# Finishline_Controller.net
KiCad netlist of a schematic drawn in EAGLE
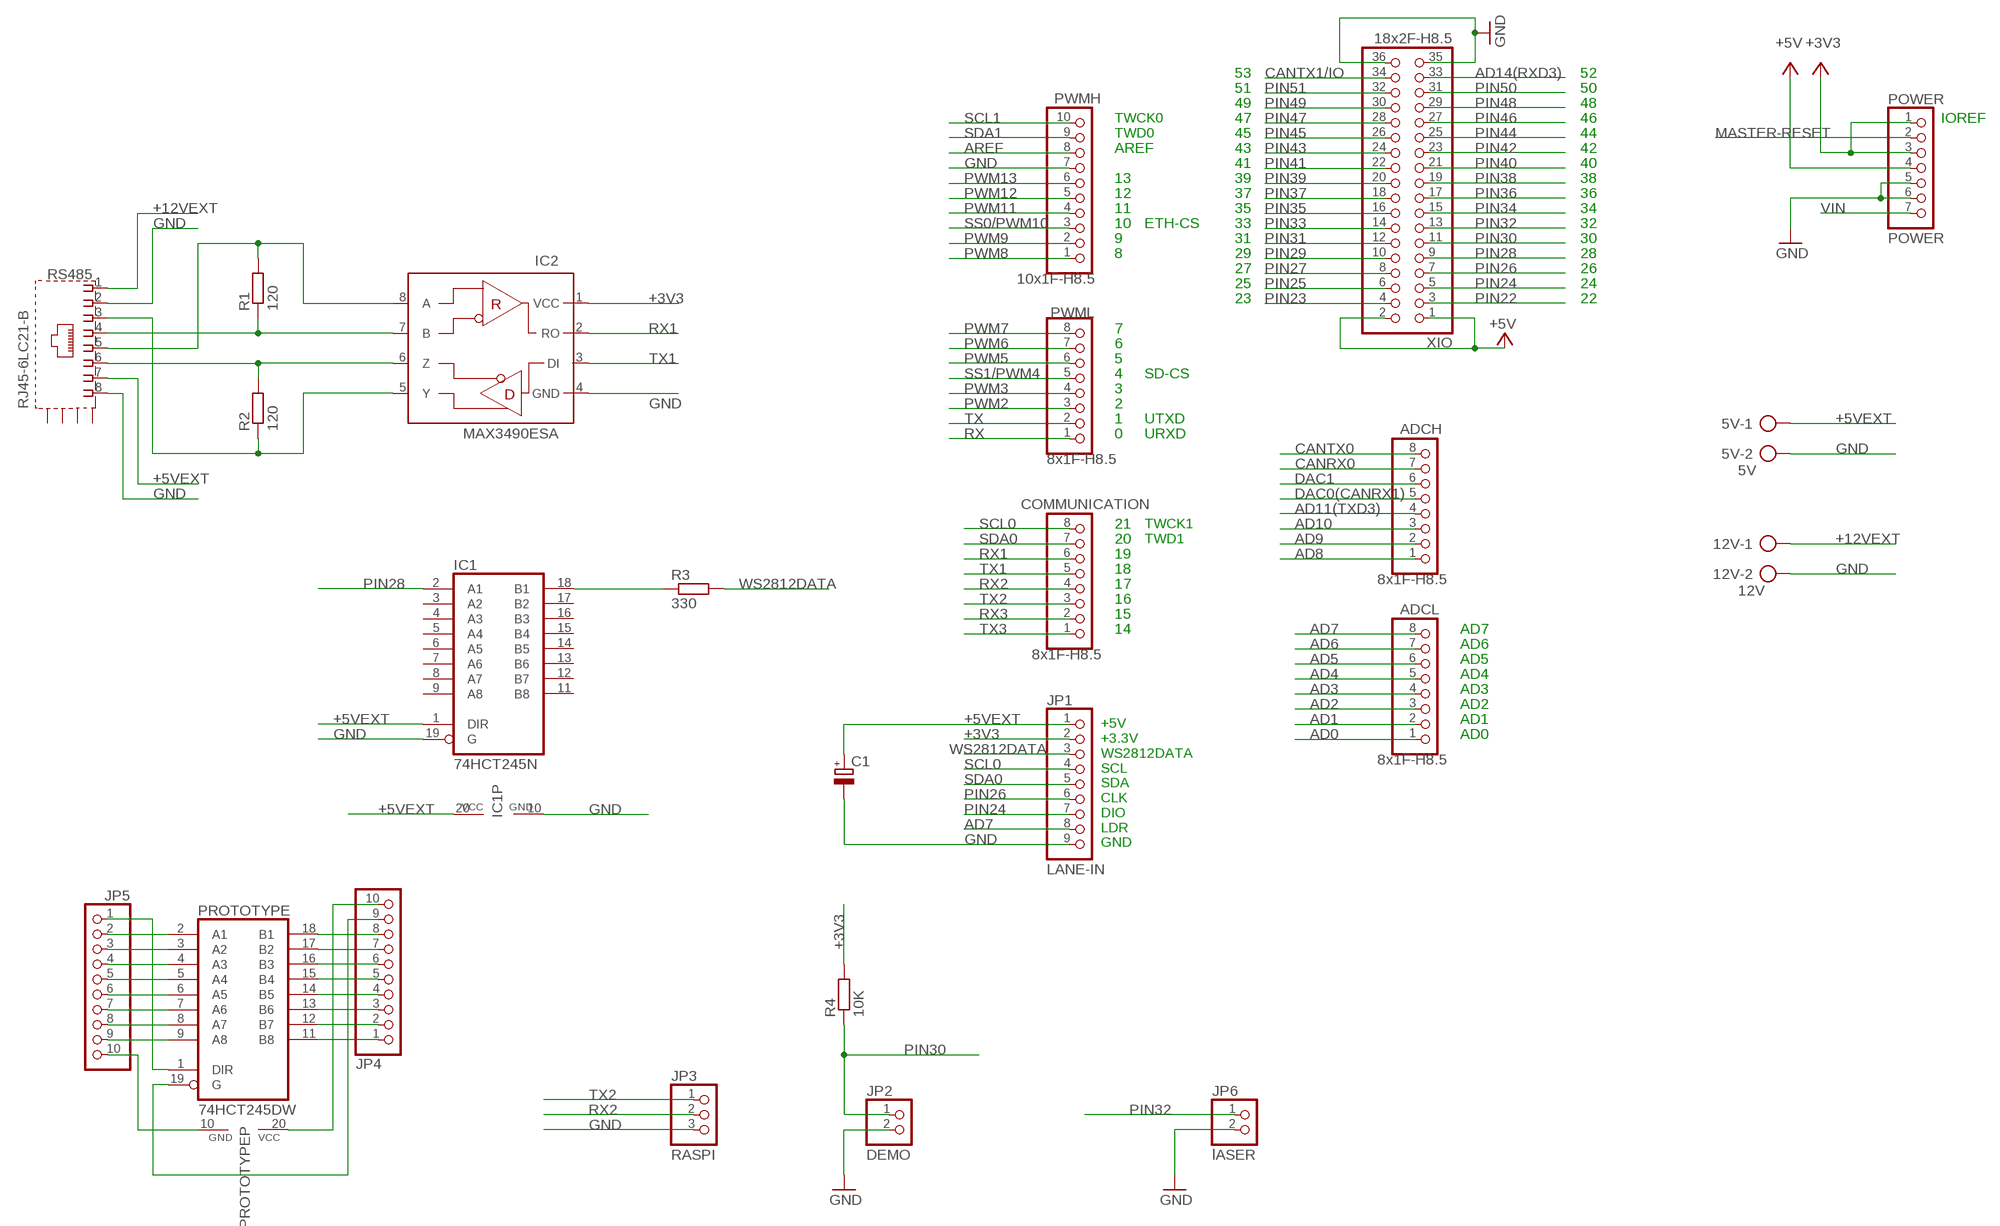
[diagram p0: schematic, sheet 1]

(export (version "E")
  (design (tool "Eeschema 10.0.6"))
  (components
    (comp (ref "5V")
      (value "5V")
      (footprint "eagle-import:AK300_2")
      (libsource (lib "eagle-import") (part "AK300/2"))
    )
    (comp (ref "12V")
      (value "12V")
      (footprint "eagle-import:AK300_2")
      (libsource (lib "eagle-import") (part "AK300/2"))
    )
    (comp (ref "ADCH")
      (value "8x1F-H8.5")
      (footprint "eagle-import:1X08")
      (libsource (lib "eagle-import") (part "PINHD-1X8"))
    )
    (comp (ref "ADCL")
      (value "8x1F-H8.5")
      (footprint "eagle-import:1X08")
      (libsource (lib "eagle-import") (part "PINHD-1X8"))
    )
    (comp (ref "C1")
      (value "CPOL-EUE5-10.5")
      (footprint "eagle-import:E5-10,5")
      (libsource (lib "eagle-import") (part "CPOL-EUE5-10.5"))
    )
    (comp (ref "COMMUNICATION")
      (value "8x1F-H8.5")
      (footprint "eagle-import:1X08")
      (libsource (lib "eagle-import") (part "PINHD-1X8"))
    )
    (comp (ref "IC1")
      (value "74HCT245N")
      (footprint "eagle-import:DIL20")
      (libsource (lib "eagle-import") (part "74245NHCT"))
    )
    (comp (ref "IC2")
      (value "MAX3490ESA")
      (footprint "eagle-import:SO08")
      (libsource (lib "eagle-import") (part "MAX3490ESA"))
    )
    (comp (ref "JP1")
      (value "LANE-IN")
      (footprint "eagle-import:1X09")
      (libsource (lib "eagle-import") (part "PINHD-1X9"))
    )
    (comp (ref "JP2")
      (value "DEMO")
      (footprint "eagle-import:1X02")
      (libsource (lib "eagle-import") (part "PINHD-1X2"))
    )
    (comp (ref "JP3")
      (value "RASPI")
      (footprint "eagle-import:1X03")
      (libsource (lib "eagle-import") (part "PINHD-1X3"))
    )
    (comp (ref "JP4")
      (value "PINHD-1X10")
      (footprint "eagle-import:1X10")
      (libsource (lib "eagle-import") (part "pinhead_PINHD-1X10"))
    )
    (comp (ref "JP5")
      (value "PINHD-1X10")
      (footprint "eagle-import:1X10")
      (libsource (lib "eagle-import") (part "pinhead_PINHD-1X10"))
    )
    (comp (ref "JP6")
      (value "lASER")
      (footprint "eagle-import:1X02")
      (libsource (lib "eagle-import") (part "PINHD-1X2"))
    )
    (comp (ref "POWER")
      (value "POWER")
      (footprint "eagle-import:1X07")
      (libsource (lib "eagle-import") (part "PINHD-1X7"))
    )
    (comp (ref "PROTOTYPE")
      (value "74HCT245DW")
      (footprint "eagle-import:SO20W")
      (libsource (lib "eagle-import") (part "74245DWHCT"))
    )
    (comp (ref "PWMH")
      (value "10x1F-H8.5")
      (footprint "eagle-import:1X10")
      (libsource (lib "eagle-import") (part "PINHD-1X10"))
    )
    (comp (ref "PWML")
      (value "8x1F-H8.5")
      (footprint "eagle-import:1X08")
      (libsource (lib "eagle-import") (part "PINHD-1X8"))
    )
    (comp (ref "R1")
      (value "120")
      (footprint "eagle-import:R0805")
      (libsource (lib "eagle-import") (part "R-EU_R0805"))
    )
    (comp (ref "R2")
      (value "120")
      (footprint "eagle-import:R0805")
      (libsource (lib "eagle-import") (part "R-EU_R0805"))
    )
    (comp (ref "R3")
      (value "330")
      (footprint "eagle-import:R0805")
      (libsource (lib "eagle-import") (part "R-EU_R0805"))
    )
    (comp (ref "R4")
      (value "10K")
      (footprint "eagle-import:R0805")
      (libsource (lib "eagle-import") (part "R-EU_R0805"))
    )
    (comp (ref "RS485")
      (value "RJ45-6LC21-B")
      (footprint "eagle-import:RJ45-SHIELD1")
      (libsource (lib "eagle-import") (part "RJ4521-B-6LC"))
    )
    (comp (ref "XIO")
      (value "18x2F-H8.5")
      (footprint "eagle-import:2X18")
      (libsource (lib "eagle-import") (part "PINHD-2X18"))
    )
  )
  (nets
    (net (code "1") (name "+3V3") (class "Default")
      (node (ref "IC2") (pin "1") (pinfunction "VCC_1") (pintype "power_in"))
      (node (ref "JP1") (pin "2") (pinfunction "2_2") (pintype "passive"))
      (node (ref "POWER") (pin "1") (pinfunction "1_1") (pintype "passive"))
      (node (ref "POWER") (pin "3") (pinfunction "3_3") (pintype "passive"))
      (node (ref "R4") (pin "2") (pinfunction "2_2") (pintype "passive"))
    )
    (net (code "2") (name "+5V") (class "Default")
      (node (ref "POWER") (pin "4") (pinfunction "4_4") (pintype "passive"))
      (node (ref "XIO") (pin "1") (pinfunction "1_1") (pintype "passive"))
      (node (ref "XIO") (pin "2") (pinfunction "2_2") (pintype "passive"))
    )
    (net (code "3") (name "/+5VEXT") (class "Default")
      (node (ref "5V") (pin "1") (pinfunction "KL_1") (pintype "passive"))
      (node (ref "C1") (pin "+") (pinfunction "+_+") (pintype "passive"))
      (node (ref "IC1") (pin "1") (pinfunction "DIR_1") (pintype "input"))
      (node (ref "IC1") (pin "20") (pinfunction "VCC_20") (pintype "power_in"))
      (node (ref "JP1") (pin "1") (pinfunction "1_1") (pintype "passive"))
      (node (ref "RS485") (pin "7") (pinfunction "7_7") (pintype "passive"))
    )
    (net (code "4") (name "/+12VEXT") (class "Default")
      (node (ref "12V") (pin "1") (pinfunction "KL_1") (pintype "passive"))
      (node (ref "RS485") (pin "1") (pinfunction "1_1") (pintype "passive"))
    )
    (net (code "5") (name "/AD0") (class "Default")
      (node (ref "ADCL") (pin "1") (pinfunction "1_1") (pintype "passive"))
    )
    (net (code "6") (name "/AD1") (class "Default")
      (node (ref "ADCL") (pin "2") (pinfunction "2_2") (pintype "passive"))
    )
    (net (code "7") (name "/AD2") (class "Default")
      (node (ref "ADCL") (pin "3") (pinfunction "3_3") (pintype "passive"))
    )
    (net (code "8") (name "/AD3") (class "Default")
      (node (ref "ADCL") (pin "4") (pinfunction "4_4") (pintype "passive"))
    )
    (net (code "9") (name "/AD4") (class "Default")
      (node (ref "ADCL") (pin "5") (pinfunction "5_5") (pintype "passive"))
    )
    (net (code "10") (name "/AD5") (class "Default")
      (node (ref "ADCL") (pin "6") (pinfunction "6_6") (pintype "passive"))
    )
    (net (code "11") (name "/AD6") (class "Default")
      (node (ref "ADCL") (pin "7") (pinfunction "7_7") (pintype "passive"))
    )
    (net (code "12") (name "/AD7") (class "Default")
      (node (ref "ADCL") (pin "8") (pinfunction "8_8") (pintype "passive"))
      (node (ref "JP1") (pin "8") (pinfunction "8_8") (pintype "passive"))
    )
    (net (code "13") (name "/AD8") (class "Default")
      (node (ref "ADCH") (pin "1") (pinfunction "1_1") (pintype "passive"))
    )
    (net (code "14") (name "/AD9") (class "Default")
      (node (ref "ADCH") (pin "2") (pinfunction "2_2") (pintype "passive"))
    )
    (net (code "15") (name "/AD10") (class "Default")
      (node (ref "ADCH") (pin "3") (pinfunction "3_3") (pintype "passive"))
    )
    (net (code "16") (name "/AD11(TXD3)") (class "Default")
      (node (ref "ADCH") (pin "4") (pinfunction "4_4") (pintype "passive"))
    )
    (net (code "17") (name "/AD14(RXD3)") (class "Default")
      (node (ref "XIO") (pin "33") (pinfunction "33_33") (pintype "passive"))
    )
    (net (code "18") (name "/AREF") (class "Default")
      (node (ref "PWMH") (pin "8") (pinfunction "8_8") (pintype "passive"))
    )
    (net (code "19") (name "/CANRX0") (class "Default")
      (node (ref "ADCH") (pin "7") (pinfunction "7_7") (pintype "passive"))
    )
    (net (code "20") (name "/CANTX0") (class "Default")
      (node (ref "ADCH") (pin "8") (pinfunction "8_8") (pintype "passive"))
    )
    (net (code "21") (name "/CANTX1{slash}IO") (class "Default")
      (node (ref "XIO") (pin "34") (pinfunction "34_34") (pintype "passive"))
    )
    (net (code "22") (name "/DAC0(CANRX1)") (class "Default")
      (node (ref "ADCH") (pin "5") (pinfunction "5_5") (pintype "passive"))
    )
    (net (code "23") (name "/DAC1") (class "Default")
      (node (ref "ADCH") (pin "6") (pinfunction "6_6") (pintype "passive"))
    )
    (net (code "24") (name "/MASTER-RESET") (class "Default")
      (node (ref "POWER") (pin "2") (pinfunction "2_2") (pintype "passive"))
    )
    (net (code "25") (name "/PIN22") (class "Default")
      (node (ref "XIO") (pin "3") (pinfunction "3_3") (pintype "passive"))
    )
    (net (code "26") (name "/PIN23") (class "Default")
      (node (ref "XIO") (pin "4") (pinfunction "4_4") (pintype "passive"))
    )
    (net (code "27") (name "/PIN24") (class "Default")
      (node (ref "JP1") (pin "7") (pinfunction "7_7") (pintype "passive"))
      (node (ref "XIO") (pin "5") (pinfunction "5_5") (pintype "passive"))
    )
    (net (code "28") (name "/PIN25") (class "Default")
      (node (ref "XIO") (pin "6") (pinfunction "6_6") (pintype "passive"))
    )
    (net (code "29") (name "/PIN26") (class "Default")
      (node (ref "JP1") (pin "6") (pinfunction "6_6") (pintype "passive"))
      (node (ref "XIO") (pin "7") (pinfunction "7_7") (pintype "passive"))
    )
    (net (code "30") (name "/PIN27") (class "Default")
      (node (ref "XIO") (pin "8") (pinfunction "8_8") (pintype "passive"))
    )
    (net (code "31") (name "/PIN28") (class "Default")
      (node (ref "IC1") (pin "2") (pinfunction "A1_2") (pintype "bidirectional"))
      (node (ref "XIO") (pin "9") (pinfunction "9_9") (pintype "passive"))
    )
    (net (code "32") (name "/PIN29") (class "Default")
      (node (ref "XIO") (pin "10") (pinfunction "10_10") (pintype "passive"))
    )
    (net (code "33") (name "/PIN30") (class "Default")
      (node (ref "JP2") (pin "1") (pinfunction "1_1") (pintype "passive"))
      (node (ref "R4") (pin "1") (pinfunction "1_1") (pintype "passive"))
      (node (ref "XIO") (pin "11") (pinfunction "11_11") (pintype "passive"))
    )
    (net (code "34") (name "/PIN31") (class "Default")
      (node (ref "XIO") (pin "12") (pinfunction "12_12") (pintype "passive"))
    )
    (net (code "35") (name "/PIN32") (class "Default")
      (node (ref "JP6") (pin "1") (pinfunction "1_1") (pintype "passive"))
      (node (ref "XIO") (pin "13") (pinfunction "13_13") (pintype "passive"))
    )
    (net (code "36") (name "/PIN33") (class "Default")
      (node (ref "XIO") (pin "14") (pinfunction "14_14") (pintype "passive"))
    )
    (net (code "37") (name "/PIN34") (class "Default")
      (node (ref "XIO") (pin "15") (pinfunction "15_15") (pintype "passive"))
    )
    (net (code "38") (name "/PIN35") (class "Default")
      (node (ref "XIO") (pin "16") (pinfunction "16_16") (pintype "passive"))
    )
    (net (code "39") (name "/PIN36") (class "Default")
      (node (ref "XIO") (pin "17") (pinfunction "17_17") (pintype "passive"))
    )
    (net (code "40") (name "/PIN37") (class "Default")
      (node (ref "XIO") (pin "18") (pinfunction "18_18") (pintype "passive"))
    )
    (net (code "41") (name "/PIN38") (class "Default")
      (node (ref "XIO") (pin "19") (pinfunction "19_19") (pintype "passive"))
    )
    (net (code "42") (name "/PIN39") (class "Default")
      (node (ref "XIO") (pin "20") (pinfunction "20_20") (pintype "passive"))
    )
    (net (code "43") (name "/PIN40") (class "Default")
      (node (ref "XIO") (pin "21") (pinfunction "21_21") (pintype "passive"))
    )
    (net (code "44") (name "/PIN41") (class "Default")
      (node (ref "XIO") (pin "22") (pinfunction "22_22") (pintype "passive"))
    )
    (net (code "45") (name "/PIN42") (class "Default")
      (node (ref "XIO") (pin "23") (pinfunction "23_23") (pintype "passive"))
    )
    (net (code "46") (name "/PIN43") (class "Default")
      (node (ref "XIO") (pin "24") (pinfunction "24_24") (pintype "passive"))
    )
    (net (code "47") (name "/PIN44") (class "Default")
      (node (ref "XIO") (pin "25") (pinfunction "25_25") (pintype "passive"))
    )
    (net (code "48") (name "/PIN45") (class "Default")
      (node (ref "XIO") (pin "26") (pinfunction "26_26") (pintype "passive"))
    )
    (net (code "49") (name "/PIN46") (class "Default")
      (node (ref "XIO") (pin "27") (pinfunction "27_27") (pintype "passive"))
    )
    (net (code "50") (name "/PIN47") (class "Default")
      (node (ref "XIO") (pin "28") (pinfunction "28_28") (pintype "passive"))
    )
    (net (code "51") (name "/PIN48") (class "Default")
      (node (ref "XIO") (pin "29") (pinfunction "29_29") (pintype "passive"))
    )
    (net (code "52") (name "/PIN49") (class "Default")
      (node (ref "XIO") (pin "30") (pinfunction "30_30") (pintype "passive"))
    )
    (net (code "53") (name "/PIN50") (class "Default")
      (node (ref "XIO") (pin "31") (pinfunction "31_31") (pintype "passive"))
    )
    (net (code "54") (name "/PIN51") (class "Default")
      (node (ref "XIO") (pin "32") (pinfunction "32_32") (pintype "passive"))
    )
    (net (code "55") (name "/PWM2") (class "Default")
      (node (ref "PWML") (pin "3") (pinfunction "3_3") (pintype "passive"))
    )
    (net (code "56") (name "/PWM3") (class "Default")
      (node (ref "PWML") (pin "4") (pinfunction "4_4") (pintype "passive"))
    )
    (net (code "57") (name "/PWM5") (class "Default")
      (node (ref "PWML") (pin "6") (pinfunction "6_6") (pintype "passive"))
    )
    (net (code "58") (name "/PWM6") (class "Default")
      (node (ref "PWML") (pin "7") (pinfunction "7_7") (pintype "passive"))
    )
    (net (code "59") (name "/PWM7") (class "Default")
      (node (ref "PWML") (pin "8") (pinfunction "8_8") (pintype "passive"))
    )
    (net (code "60") (name "/PWM8") (class "Default")
      (node (ref "PWMH") (pin "1") (pinfunction "1_1") (pintype "passive"))
    )
    (net (code "61") (name "/PWM9") (class "Default")
      (node (ref "PWMH") (pin "2") (pinfunction "2_2") (pintype "passive"))
    )
    (net (code "62") (name "/PWM11") (class "Default")
      (node (ref "PWMH") (pin "4") (pinfunction "4_4") (pintype "passive"))
    )
    (net (code "63") (name "/PWM12") (class "Default")
      (node (ref "PWMH") (pin "5") (pinfunction "5_5") (pintype "passive"))
    )
    (net (code "64") (name "/PWM13") (class "Default")
      (node (ref "PWMH") (pin "6") (pinfunction "6_6") (pintype "passive"))
    )
    (net (code "65") (name "/RX") (class "Default")
      (node (ref "PWML") (pin "1") (pinfunction "1_1") (pintype "passive"))
    )
    (net (code "66") (name "/RX1") (class "Default")
      (node (ref "COMMUNICATION") (pin "6") (pinfunction "6_6") (pintype "passive"))
      (node (ref "IC2") (pin "2") (pinfunction "RO_2") (pintype "output"))
    )
    (net (code "67") (name "/RX2") (class "Default")
      (node (ref "COMMUNICATION") (pin "4") (pinfunction "4_4") (pintype "passive"))
      (node (ref "JP3") (pin "2") (pinfunction "2_2") (pintype "passive"))
    )
    (net (code "68") (name "/RX3") (class "Default")
      (node (ref "COMMUNICATION") (pin "2") (pinfunction "2_2") (pintype "passive"))
    )
    (net (code "69") (name "/SCL0") (class "Default")
      (node (ref "COMMUNICATION") (pin "8") (pinfunction "8_8") (pintype "passive"))
      (node (ref "JP1") (pin "4") (pinfunction "4_4") (pintype "passive"))
    )
    (net (code "70") (name "/SCL1") (class "Default")
      (node (ref "PWMH") (pin "10") (pinfunction "10_10") (pintype "passive"))
    )
    (net (code "71") (name "/SDA0") (class "Default")
      (node (ref "COMMUNICATION") (pin "7") (pinfunction "7_7") (pintype "passive"))
      (node (ref "JP1") (pin "5") (pinfunction "5_5") (pintype "passive"))
    )
    (net (code "72") (name "/SDA1") (class "Default")
      (node (ref "PWMH") (pin "9") (pinfunction "9_9") (pintype "passive"))
    )
    (net (code "73") (name "/SS0{slash}PWM10") (class "Default")
      (node (ref "PWMH") (pin "3") (pinfunction "3_3") (pintype "passive"))
    )
    (net (code "74") (name "/SS1{slash}PWM4") (class "Default")
      (node (ref "PWML") (pin "5") (pinfunction "5_5") (pintype "passive"))
    )
    (net (code "75") (name "/TX") (class "Default")
      (node (ref "PWML") (pin "2") (pinfunction "2_2") (pintype "passive"))
    )
    (net (code "76") (name "/TX1") (class "Default")
      (node (ref "COMMUNICATION") (pin "5") (pinfunction "5_5") (pintype "passive"))
      (node (ref "IC2") (pin "3") (pinfunction "DI_3") (pintype "input"))
    )
    (net (code "77") (name "/TX2") (class "Default")
      (node (ref "COMMUNICATION") (pin "3") (pinfunction "3_3") (pintype "passive"))
      (node (ref "JP3") (pin "1") (pinfunction "1_1") (pintype "passive"))
    )
    (net (code "78") (name "/TX3") (class "Default")
      (node (ref "COMMUNICATION") (pin "1") (pinfunction "1_1") (pintype "passive"))
    )
    (net (code "79") (name "/VIN") (class "Default")
      (node (ref "POWER") (pin "7") (pinfunction "7_7") (pintype "passive"))
    )
    (net (code "80") (name "/WS2812DATA") (class "Default")
      (node (ref "JP1") (pin "3") (pinfunction "3_3") (pintype "passive"))
      (node (ref "R3") (pin "2") (pinfunction "2_2") (pintype "passive"))
    )
    (net (code "81") (name "GND") (class "Default")
      (node (ref "12V") (pin "2") (pinfunction "KL_2") (pintype "passive"))
      (node (ref "5V") (pin "2") (pinfunction "KL_2") (pintype "passive"))
      (node (ref "C1") (pin "-") (pinfunction "-_-") (pintype "passive"))
      (node (ref "IC1") (pin "10") (pinfunction "GND_10") (pintype "power_in"))
      (node (ref "IC1") (pin "19") (pinfunction "G_19") (pintype "input"))
      (node (ref "IC2") (pin "4") (pinfunction "GND_4") (pintype "power_in"))
      (node (ref "JP1") (pin "9") (pinfunction "9_9") (pintype "passive"))
      (node (ref "JP2") (pin "2") (pinfunction "2_2") (pintype "passive"))
      (node (ref "JP3") (pin "3") (pinfunction "3_3") (pintype "passive"))
      (node (ref "JP6") (pin "2") (pinfunction "2_2") (pintype "passive"))
      (node (ref "POWER") (pin "5") (pinfunction "5_5") (pintype "passive"))
      (node (ref "POWER") (pin "6") (pinfunction "6_6") (pintype "passive"))
      (node (ref "PWMH") (pin "7") (pinfunction "7_7") (pintype "passive"))
      (node (ref "RS485") (pin "2") (pinfunction "2_2") (pintype "passive"))
      (node (ref "RS485") (pin "8") (pinfunction "8_8") (pintype "passive"))
      (node (ref "XIO") (pin "35") (pinfunction "35_35") (pintype "passive"))
      (node (ref "XIO") (pin "36") (pinfunction "36_36") (pintype "passive"))
    )
    (net (code "82") (name "Net-(IC1A-B1)") (class "Default")
      (node (ref "IC1") (pin "18") (pinfunction "B1_18") (pintype "bidirectional"))
      (node (ref "R3") (pin "1") (pinfunction "1_1") (pintype "passive"))
    )
    (net (code "83") (name "Net-(IC2-A)") (class "Default")
      (node (ref "IC2") (pin "8") (pinfunction "A_8") (pintype "input"))
      (node (ref "R1") (pin "2") (pinfunction "2_2") (pintype "passive"))
      (node (ref "RS485") (pin "5") (pinfunction "5_5") (pintype "passive"))
    )
    (net (code "84") (name "Net-(IC2-B)") (class "Default")
      (node (ref "IC2") (pin "7") (pinfunction "B_7") (pintype "input"))
      (node (ref "R1") (pin "1") (pinfunction "1_1") (pintype "passive"))
      (node (ref "RS485") (pin "4") (pinfunction "4_4") (pintype "passive"))
    )
    (net (code "85") (name "Net-(IC2-Y)") (class "Default")
      (node (ref "IC2") (pin "5") (pinfunction "Y_5") (pintype "output"))
      (node (ref "R2") (pin "1") (pinfunction "1_1") (pintype "passive"))
      (node (ref "RS485") (pin "3") (pinfunction "3_3") (pintype "passive"))
    )
    (net (code "86") (name "Net-(IC2-Z)") (class "Default")
      (node (ref "IC2") (pin "6") (pinfunction "Z_6") (pintype "output"))
      (node (ref "R2") (pin "2") (pinfunction "2_2") (pintype "passive"))
      (node (ref "RS485") (pin "6") (pinfunction "6_6") (pintype "passive"))
    )
    (net (code "87") (name "Net-(PROTOTYPEA-A1)") (class "Default")
      (node (ref "JP5") (pin "2") (pinfunction "2_2") (pintype "passive"))
      (node (ref "PROTOTYPE") (pin "2") (pinfunction "A1_2") (pintype "bidirectional"))
    )
    (net (code "88") (name "Net-(PROTOTYPEA-A2)") (class "Default")
      (node (ref "JP5") (pin "3") (pinfunction "3_3") (pintype "passive"))
      (node (ref "PROTOTYPE") (pin "3") (pinfunction "A2_3") (pintype "bidirectional"))
    )
    (net (code "89") (name "Net-(PROTOTYPEA-A3)") (class "Default")
      (node (ref "JP5") (pin "4") (pinfunction "4_4") (pintype "passive"))
      (node (ref "PROTOTYPE") (pin "4") (pinfunction "A3_4") (pintype "bidirectional"))
    )
    (net (code "90") (name "Net-(PROTOTYPEA-A4)") (class "Default")
      (node (ref "JP5") (pin "5") (pinfunction "5_5") (pintype "passive"))
      (node (ref "PROTOTYPE") (pin "5") (pinfunction "A4_5") (pintype "bidirectional"))
    )
    (net (code "91") (name "Net-(PROTOTYPEA-A5)") (class "Default")
      (node (ref "JP5") (pin "6") (pinfunction "6_6") (pintype "passive"))
      (node (ref "PROTOTYPE") (pin "6") (pinfunction "A5_6") (pintype "bidirectional"))
    )
    (net (code "92") (name "Net-(PROTOTYPEA-A6)") (class "Default")
      (node (ref "JP5") (pin "7") (pinfunction "7_7") (pintype "passive"))
      (node (ref "PROTOTYPE") (pin "7") (pinfunction "A6_7") (pintype "bidirectional"))
    )
    (net (code "93") (name "Net-(PROTOTYPEA-A7)") (class "Default")
      (node (ref "JP5") (pin "8") (pinfunction "8_8") (pintype "passive"))
      (node (ref "PROTOTYPE") (pin "8") (pinfunction "A7_8") (pintype "bidirectional"))
    )
    (net (code "94") (name "Net-(PROTOTYPEA-A8)") (class "Default")
      (node (ref "JP5") (pin "9") (pinfunction "9_9") (pintype "passive"))
      (node (ref "PROTOTYPE") (pin "9") (pinfunction "A8_9") (pintype "bidirectional"))
    )
    (net (code "95") (name "Net-(PROTOTYPEA-B1)") (class "Default")
      (node (ref "JP4") (pin "8") (pinfunction "8_8") (pintype "passive"))
      (node (ref "PROTOTYPE") (pin "18") (pinfunction "B1_18") (pintype "bidirectional"))
    )
    (net (code "96") (name "Net-(PROTOTYPEA-B2)") (class "Default")
      (node (ref "JP4") (pin "7") (pinfunction "7_7") (pintype "passive"))
      (node (ref "PROTOTYPE") (pin "17") (pinfunction "B2_17") (pintype "bidirectional"))
    )
    (net (code "97") (name "Net-(PROTOTYPEA-B3)") (class "Default")
      (node (ref "JP4") (pin "6") (pinfunction "6_6") (pintype "passive"))
      (node (ref "PROTOTYPE") (pin "16") (pinfunction "B3_16") (pintype "bidirectional"))
    )
    (net (code "98") (name "Net-(PROTOTYPEA-B4)") (class "Default")
      (node (ref "JP4") (pin "5") (pinfunction "5_5") (pintype "passive"))
      (node (ref "PROTOTYPE") (pin "15") (pinfunction "B4_15") (pintype "bidirectional"))
    )
    (net (code "99") (name "Net-(PROTOTYPEA-B5)") (class "Default")
      (node (ref "JP4") (pin "4") (pinfunction "4_4") (pintype "passive"))
      (node (ref "PROTOTYPE") (pin "14") (pinfunction "B5_14") (pintype "bidirectional"))
    )
    (net (code "100") (name "Net-(PROTOTYPEA-B6)") (class "Default")
      (node (ref "JP4") (pin "3") (pinfunction "3_3") (pintype "passive"))
      (node (ref "PROTOTYPE") (pin "13") (pinfunction "B6_13") (pintype "bidirectional"))
    )
    (net (code "101") (name "Net-(PROTOTYPEA-B7)") (class "Default")
      (node (ref "JP4") (pin "2") (pinfunction "2_2") (pintype "passive"))
      (node (ref "PROTOTYPE") (pin "12") (pinfunction "B7_12") (pintype "bidirectional"))
    )
    (net (code "102") (name "Net-(PROTOTYPEA-B8)") (class "Default")
      (node (ref "JP4") (pin "1") (pinfunction "1_1") (pintype "passive"))
      (node (ref "PROTOTYPE") (pin "11") (pinfunction "B8_11") (pintype "bidirectional"))
    )
    (net (code "103") (name "Net-(PROTOTYPEA-DIR)") (class "Default")
      (node (ref "JP5") (pin "1") (pinfunction "1_1") (pintype "passive"))
      (node (ref "PROTOTYPE") (pin "1") (pinfunction "DIR_1") (pintype "input"))
    )
    (net (code "104") (name "Net-(PROTOTYPEA-G)") (class "Default")
      (node (ref "JP4") (pin "9") (pinfunction "9_9") (pintype "passive"))
      (node (ref "PROTOTYPE") (pin "19") (pinfunction "G_19") (pintype "input"))
    )
    (net (code "105") (name "Net-(PROTOTYPEB-GND)") (class "Default")
      (node (ref "JP5") (pin "10") (pinfunction "10_10") (pintype "passive"))
      (node (ref "PROTOTYPE") (pin "10") (pinfunction "GND_10") (pintype "power_in"))
    )
    (net (code "106") (name "Net-(PROTOTYPEB-VCC)") (class "Default")
      (node (ref "JP4") (pin "10") (pinfunction "10_10") (pintype "passive"))
      (node (ref "PROTOTYPE") (pin "20") (pinfunction "VCC_20") (pintype "power_in"))
    )
    (net (code "107") (name "unconnected-(IC1A-A2-Pad3)") (class "Default")
      (node (ref "IC1") (pin "3") (pinfunction "A2_3") (pintype "bidirectional"))
    )
    (net (code "108") (name "unconnected-(IC1A-A3-Pad4)") (class "Default")
      (node (ref "IC1") (pin "4") (pinfunction "A3_4") (pintype "bidirectional"))
    )
    (net (code "109") (name "unconnected-(IC1A-A4-Pad5)") (class "Default")
      (node (ref "IC1") (pin "5") (pinfunction "A4_5") (pintype "bidirectional"))
    )
    (net (code "110") (name "unconnected-(IC1A-A5-Pad6)") (class "Default")
      (node (ref "IC1") (pin "6") (pinfunction "A5_6") (pintype "bidirectional"))
    )
    (net (code "111") (name "unconnected-(IC1A-A6-Pad7)") (class "Default")
      (node (ref "IC1") (pin "7") (pinfunction "A6_7") (pintype "bidirectional"))
    )
    (net (code "112") (name "unconnected-(IC1A-A7-Pad8)") (class "Default")
      (node (ref "IC1") (pin "8") (pinfunction "A7_8") (pintype "bidirectional"))
    )
    (net (code "113") (name "unconnected-(IC1A-A8-Pad9)") (class "Default")
      (node (ref "IC1") (pin "9") (pinfunction "A8_9") (pintype "bidirectional"))
    )
    (net (code "114") (name "unconnected-(IC1A-B2-Pad17)") (class "Default")
      (node (ref "IC1") (pin "17") (pinfunction "B2_17") (pintype "bidirectional"))
    )
    (net (code "115") (name "unconnected-(IC1A-B3-Pad16)") (class "Default")
      (node (ref "IC1") (pin "16") (pinfunction "B3_16") (pintype "bidirectional"))
    )
    (net (code "116") (name "unconnected-(IC1A-B4-Pad15)") (class "Default")
      (node (ref "IC1") (pin "15") (pinfunction "B4_15") (pintype "bidirectional"))
    )
    (net (code "117") (name "unconnected-(IC1A-B5-Pad14)") (class "Default")
      (node (ref "IC1") (pin "14") (pinfunction "B5_14") (pintype "bidirectional"))
    )
    (net (code "118") (name "unconnected-(IC1A-B6-Pad13)") (class "Default")
      (node (ref "IC1") (pin "13") (pinfunction "B6_13") (pintype "bidirectional"))
    )
    (net (code "119") (name "unconnected-(IC1A-B7-Pad12)") (class "Default")
      (node (ref "IC1") (pin "12") (pinfunction "B7_12") (pintype "bidirectional"))
    )
    (net (code "120") (name "unconnected-(IC1A-B8-Pad11)") (class "Default")
      (node (ref "IC1") (pin "11") (pinfunction "B8_11") (pintype "bidirectional"))
    )
    (net (code "121") (name "unconnected-(RS485-S-PadS1)") (class "Default")
      (node (ref "RS485") (pin "S1") (pinfunction "S_S1") (pintype "passive"))
    )
    (net (code "122") (name "unconnected-(RS485-S-PadS2)") (class "Default")
      (node (ref "RS485") (pin "S2") (pinfunction "S_S2") (pintype "passive"))
    )
    (net (code "123") (name "unconnected-(RS485-S-PadS3)") (class "Default")
      (node (ref "RS485") (pin "S3") (pinfunction "S_S3") (pintype "passive"))
    )
    (net (code "124") (name "unconnected-(RS485-S-PadS4)") (class "Default")
      (node (ref "RS485") (pin "S4") (pinfunction "S_S4") (pintype "passive"))
    )
  )
)
